# B684X.net
KiCad netlist of a schematic drawn in EAGLE
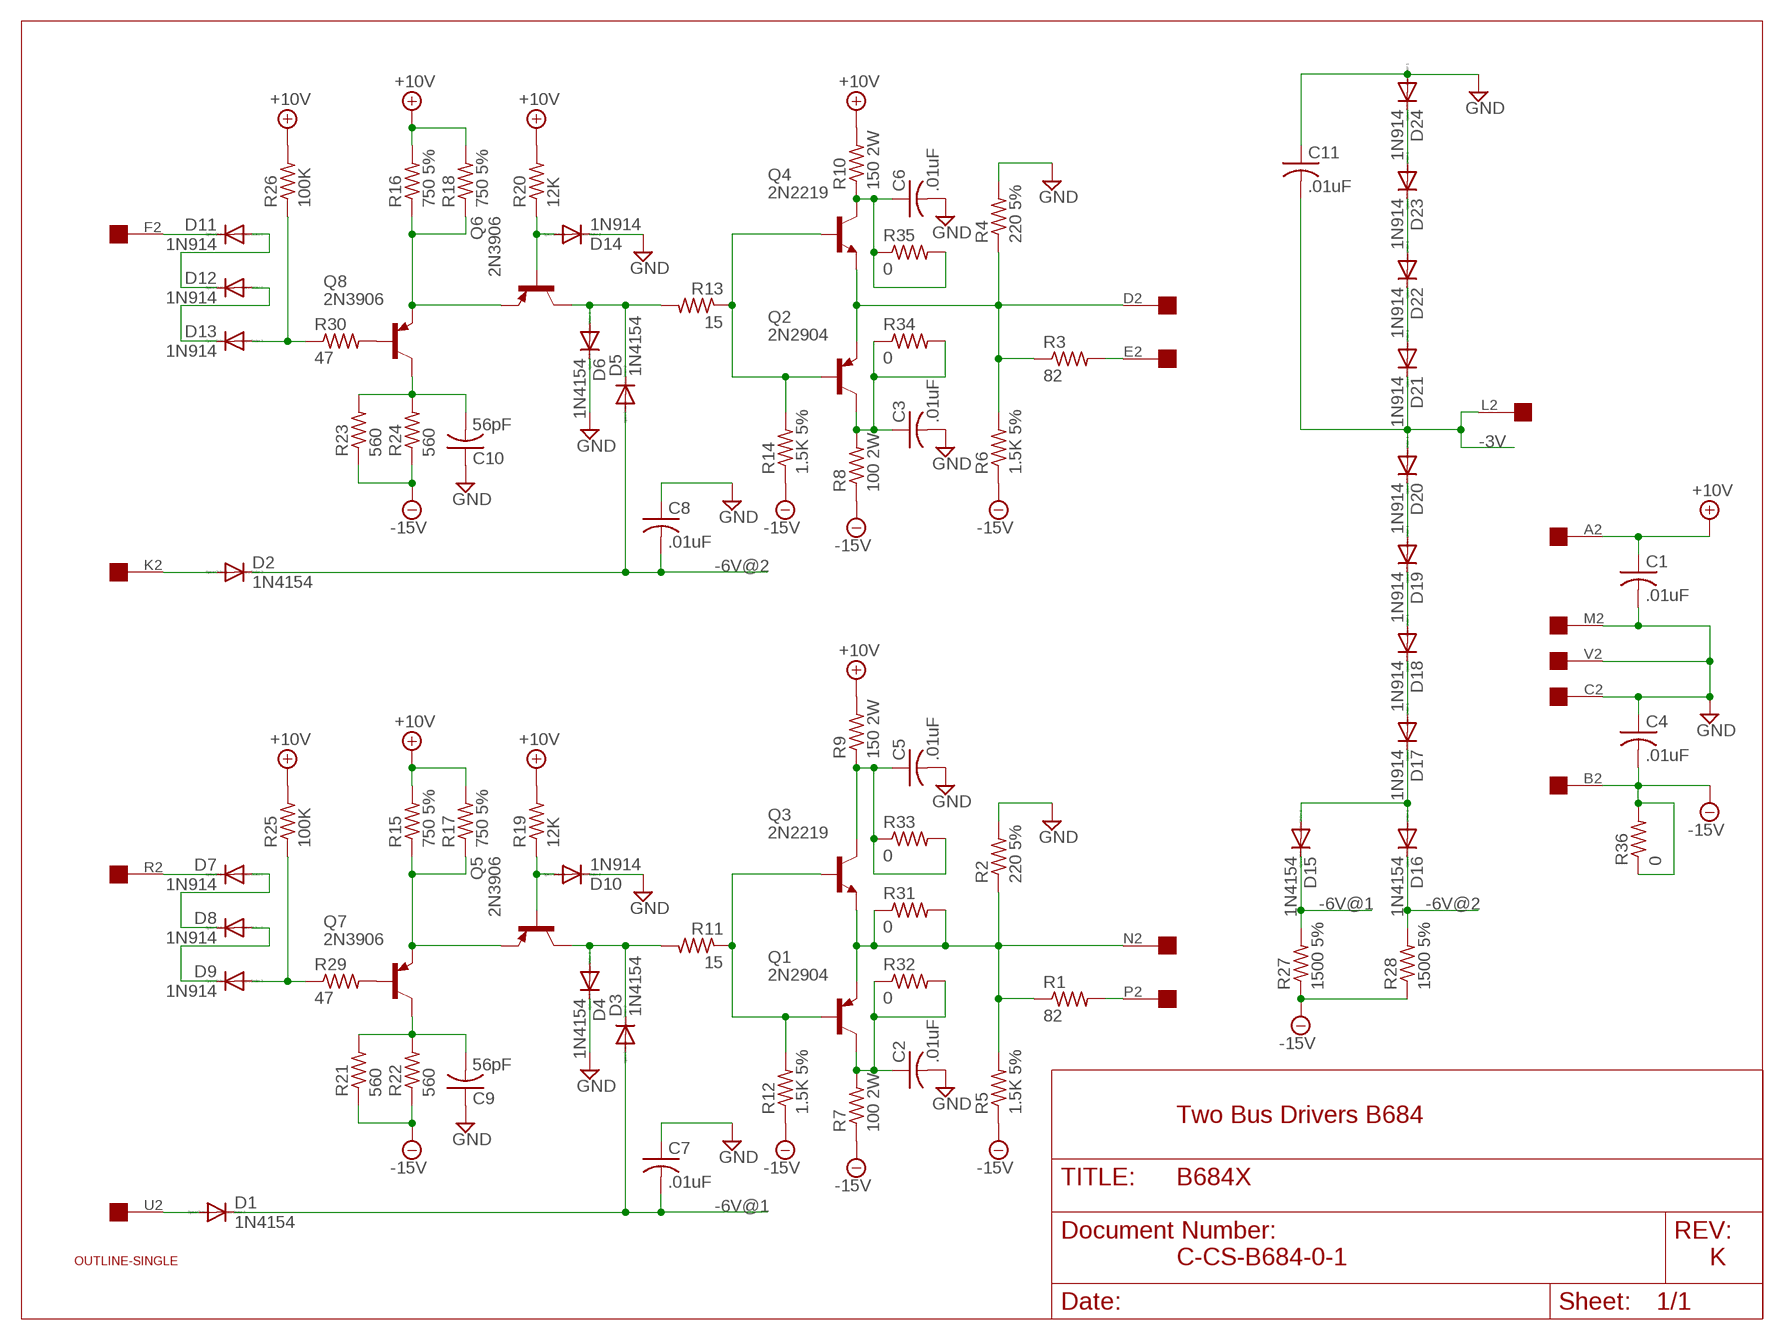
[diagram p0: schematic, sheet 1]

(export (version "E")
  (design (tool "Eeschema 10.0.6"))
  (components
    (comp (ref "C1")
      (value ".01uF")
      (footprint "eagle-import:C063-025X075")
      (libsource (lib "eagle-import") (part "C-US"))
    )
    (comp (ref "C2")
      (value ".01uF")
      (footprint "eagle-import:C063-025X075")
      (libsource (lib "eagle-import") (part "C-US"))
    )
    (comp (ref "C3")
      (value ".01uF")
      (footprint "eagle-import:C063-025X075")
      (libsource (lib "eagle-import") (part "C-US"))
    )
    (comp (ref "C4")
      (value ".01uF")
      (footprint "eagle-import:C063-025X075")
      (libsource (lib "eagle-import") (part "C-US"))
    )
    (comp (ref "C5")
      (value ".01uF")
      (footprint "eagle-import:C063-025X075")
      (libsource (lib "eagle-import") (part "C-US"))
    )
    (comp (ref "C6")
      (value ".01uF")
      (footprint "eagle-import:C063-025X075")
      (libsource (lib "eagle-import") (part "C-US"))
    )
    (comp (ref "C7")
      (value ".01uF")
      (footprint "eagle-import:C063-025X075")
      (libsource (lib "eagle-import") (part "C-US"))
    )
    (comp (ref "C8")
      (value ".01uF")
      (footprint "eagle-import:C063-025X075")
      (libsource (lib "eagle-import") (part "C-US"))
    )
    (comp (ref "C9")
      (value "56pF")
      (footprint "eagle-import:C063-025X075")
      (libsource (lib "eagle-import") (part "C-US"))
    )
    (comp (ref "C10")
      (value "56pF")
      (footprint "eagle-import:C063-025X075")
      (libsource (lib "eagle-import") (part "C-US"))
    )
    (comp (ref "C11")
      (value ".01uF")
      (footprint "eagle-import:C063-025X075")
      (libsource (lib "eagle-import") (part "C-US"))
    )
    (comp (ref "D1")
      (value "1N4154")
      (footprint "eagle-import:DO35-10")
      (libsource (lib "eagle-import") (part "1N4148DO35-10"))
    )
    (comp (ref "D2")
      (value "1N4154")
      (footprint "eagle-import:DO35-10")
      (libsource (lib "eagle-import") (part "1N4148DO35-10"))
    )
    (comp (ref "D3")
      (value "1N4154")
      (footprint "eagle-import:DO35-10")
      (libsource (lib "eagle-import") (part "1N4148DO35-10"))
    )
    (comp (ref "D4")
      (value "1N4154")
      (footprint "eagle-import:DO35-10")
      (libsource (lib "eagle-import") (part "1N4148DO35-10"))
    )
    (comp (ref "D5")
      (value "1N4154")
      (footprint "eagle-import:DO35-10")
      (libsource (lib "eagle-import") (part "1N4148DO35-10"))
    )
    (comp (ref "D6")
      (value "1N4154")
      (footprint "eagle-import:DO35-10")
      (libsource (lib "eagle-import") (part "1N4148DO35-10"))
    )
    (comp (ref "D7")
      (value "1N914")
      (footprint "eagle-import:DO35-10")
      (libsource (lib "eagle-import") (part "1N4148DO35-10"))
    )
    (comp (ref "D8")
      (value "1N914")
      (footprint "eagle-import:DO35-10")
      (libsource (lib "eagle-import") (part "1N4148DO35-10"))
    )
    (comp (ref "D9")
      (value "1N914")
      (footprint "eagle-import:DO35-10")
      (libsource (lib "eagle-import") (part "DIODE-DO35-10"))
    )
    (comp (ref "D10")
      (value "1N914")
      (footprint "eagle-import:DO35-10")
      (libsource (lib "eagle-import") (part "1N4148DO35-10"))
    )
    (comp (ref "D11")
      (value "1N914")
      (footprint "eagle-import:DO35-10")
      (libsource (lib "eagle-import") (part "1N4148DO35-10"))
    )
    (comp (ref "D12")
      (value "1N914")
      (footprint "eagle-import:DO35-10")
      (libsource (lib "eagle-import") (part "1N4148DO35-10"))
    )
    (comp (ref "D13")
      (value "1N914")
      (footprint "eagle-import:DO35-10")
      (libsource (lib "eagle-import") (part "DIODE-DO35-10"))
    )
    (comp (ref "D14")
      (value "1N914")
      (footprint "eagle-import:DO35-10")
      (libsource (lib "eagle-import") (part "1N4148DO35-10"))
    )
    (comp (ref "D15")
      (value "1N4154")
      (footprint "eagle-import:DO35-10")
      (libsource (lib "eagle-import") (part "1N4148DO35-10"))
    )
    (comp (ref "D16")
      (value "1N4154")
      (footprint "eagle-import:DO35-10")
      (libsource (lib "eagle-import") (part "1N4148DO35-10"))
    )
    (comp (ref "D17")
      (value "1N914")
      (footprint "eagle-import:DO35-10")
      (libsource (lib "eagle-import") (part "1N4148DO35-10"))
    )
    (comp (ref "D18")
      (value "1N914")
      (footprint "eagle-import:DO35-10")
      (libsource (lib "eagle-import") (part "1N4148DO35-10"))
    )
    (comp (ref "D19")
      (value "1N914")
      (footprint "eagle-import:DO35-10")
      (libsource (lib "eagle-import") (part "1N4148DO35-10"))
    )
    (comp (ref "D20")
      (value "1N914")
      (footprint "eagle-import:DO35-10")
      (libsource (lib "eagle-import") (part "1N4148DO35-10"))
    )
    (comp (ref "D21")
      (value "1N914")
      (footprint "eagle-import:DO35-10")
      (libsource (lib "eagle-import") (part "1N4148DO35-10"))
    )
    (comp (ref "D22")
      (value "1N914")
      (footprint "eagle-import:DO35-10")
      (libsource (lib "eagle-import") (part "1N4148DO35-10"))
    )
    (comp (ref "D23")
      (value "1N914")
      (footprint "eagle-import:DO35-10")
      (libsource (lib "eagle-import") (part "1N4148DO35-10"))
    )
    (comp (ref "D24")
      (value "1N914")
      (footprint "eagle-import:DO35-10")
      (libsource (lib "eagle-import") (part "1N4148DO35-10"))
    )
    (comp (ref "Q1")
      (value "2N2904")
      (footprint "eagle-import:TO39")
      (libsource (lib "eagle-import") (part "2N3637"))
    )
    (comp (ref "Q2")
      (value "2N2904")
      (footprint "eagle-import:TO39")
      (libsource (lib "eagle-import") (part "2N3637"))
    )
    (comp (ref "Q3")
      (value "2N2219")
      (footprint "eagle-import:TO5")
      (libsource (lib "eagle-import") (part "2N2219"))
    )
    (comp (ref "Q4")
      (value "2N2219")
      (footprint "eagle-import:TO5")
      (libsource (lib "eagle-import") (part "2N2219"))
    )
    (comp (ref "Q5")
      (value "2N3906")
      (footprint "eagle-import:TO39")
      (libsource (lib "eagle-import") (part "2N3637"))
    )
    (comp (ref "Q6")
      (value "2N3906")
      (footprint "eagle-import:TO39")
      (libsource (lib "eagle-import") (part "2N3637"))
    )
    (comp (ref "Q7")
      (value "2N3906")
      (footprint "eagle-import:TO39")
      (libsource (lib "eagle-import") (part "2N3637"))
    )
    (comp (ref "Q8")
      (value "2N3906")
      (footprint "eagle-import:TO39")
      (libsource (lib "eagle-import") (part "2N3637"))
    )
    (comp (ref "R1")
      (value "82")
      (footprint "eagle-import:0207_10")
      (libsource (lib "eagle-import") (part "R-US_0207/10"))
    )
    (comp (ref "R2")
      (value "220 5%")
      (footprint "eagle-import:0207_10")
      (libsource (lib "eagle-import") (part "R-US_0207/10"))
    )
    (comp (ref "R3")
      (value "82")
      (footprint "eagle-import:0207_10")
      (libsource (lib "eagle-import") (part "R-US_0207/10"))
    )
    (comp (ref "R4")
      (value "220 5%")
      (footprint "eagle-import:0207_10")
      (libsource (lib "eagle-import") (part "R-US_0207/10"))
    )
    (comp (ref "R5")
      (value "1.5K 5%")
      (footprint "eagle-import:0207_10")
      (libsource (lib "eagle-import") (part "R-US_0207/10"))
    )
    (comp (ref "R6")
      (value "1.5K 5%")
      (footprint "eagle-import:0207_10")
      (libsource (lib "eagle-import") (part "R-US_0207/10"))
    )
    (comp (ref "R7")
      (value "100 2W")
      (footprint "eagle-import:P0817_22")
      (libsource (lib "eagle-import") (part "R-US_0817/22"))
    )
    (comp (ref "R8")
      (value "100 2W")
      (footprint "eagle-import:P0817_22")
      (libsource (lib "eagle-import") (part "R-US_0817/22"))
    )
    (comp (ref "R9")
      (value "150 2W")
      (footprint "eagle-import:P0817_22")
      (libsource (lib "eagle-import") (part "R-US_0817/22"))
    )
    (comp (ref "R10")
      (value "150 2W")
      (footprint "eagle-import:P0817_22")
      (libsource (lib "eagle-import") (part "R-US_0817/22"))
    )
    (comp (ref "R11")
      (value "15")
      (footprint "eagle-import:0207_10")
      (libsource (lib "eagle-import") (part "R-US_0207/10"))
    )
    (comp (ref "R12")
      (value "1.5K 5%")
      (footprint "eagle-import:0207_10")
      (libsource (lib "eagle-import") (part "R-US_0207/10"))
    )
    (comp (ref "R13")
      (value "15")
      (footprint "eagle-import:0207_10")
      (libsource (lib "eagle-import") (part "R-US_0207/10"))
    )
    (comp (ref "R14")
      (value "1.5K 5%")
      (footprint "eagle-import:0207_10")
      (libsource (lib "eagle-import") (part "R-US_0207/10"))
    )
    (comp (ref "R15")
      (value "750 5%")
      (footprint "eagle-import:0207_10")
      (libsource (lib "eagle-import") (part "R-US_0207/10"))
    )
    (comp (ref "R16")
      (value "750 5%")
      (footprint "eagle-import:0207_10")
      (libsource (lib "eagle-import") (part "R-US_0207/10"))
    )
    (comp (ref "R17")
      (value "750 5%")
      (footprint "eagle-import:0207_10")
      (libsource (lib "eagle-import") (part "R-US_0207/10"))
    )
    (comp (ref "R18")
      (value "750 5%")
      (footprint "eagle-import:0207_10")
      (libsource (lib "eagle-import") (part "R-US_0207/10"))
    )
    (comp (ref "R19")
      (value "12K")
      (footprint "eagle-import:0207_10")
      (libsource (lib "eagle-import") (part "R-US_0207/10"))
    )
    (comp (ref "R20")
      (value "12K")
      (footprint "eagle-import:0207_10")
      (libsource (lib "eagle-import") (part "R-US_0207/10"))
    )
    (comp (ref "R21")
      (value "560")
      (footprint "eagle-import:0207_10")
      (libsource (lib "eagle-import") (part "R-US_0207/10"))
    )
    (comp (ref "R22")
      (value "560")
      (footprint "eagle-import:0207_10")
      (libsource (lib "eagle-import") (part "R-US_0207/10"))
    )
    (comp (ref "R23")
      (value "560")
      (footprint "eagle-import:0207_10")
      (libsource (lib "eagle-import") (part "R-US_0207/10"))
    )
    (comp (ref "R24")
      (value "560")
      (footprint "eagle-import:0207_10")
      (libsource (lib "eagle-import") (part "R-US_0207/10"))
    )
    (comp (ref "R25")
      (value "100K")
      (footprint "eagle-import:0207_10")
      (libsource (lib "eagle-import") (part "R-US_0207/10"))
    )
    (comp (ref "R26")
      (value "100K")
      (footprint "eagle-import:0207_10")
      (libsource (lib "eagle-import") (part "R-US_0207/10"))
    )
    (comp (ref "R27")
      (value "1500 5%")
      (footprint "eagle-import:0207_10")
      (libsource (lib "eagle-import") (part "R-US_0207/10"))
    )
    (comp (ref "R28")
      (value "1500 5%")
      (footprint "eagle-import:0207_10")
      (libsource (lib "eagle-import") (part "R-US_0207/10"))
    )
    (comp (ref "R29")
      (value "47")
      (footprint "eagle-import:0207_10")
      (libsource (lib "eagle-import") (part "R-US_0207/10"))
    )
    (comp (ref "R30")
      (value "47")
      (footprint "eagle-import:0207_10")
      (libsource (lib "eagle-import") (part "R-US_0207/10"))
    )
    (comp (ref "R31")
      (value "0")
      (footprint "eagle-import:0207_10")
      (libsource (lib "eagle-import") (part "R-US_0207/10"))
    )
    (comp (ref "R32")
      (value "0")
      (footprint "eagle-import:0207_10")
      (libsource (lib "eagle-import") (part "R-US_0207/10"))
    )
    (comp (ref "R33")
      (value "0")
      (footprint "eagle-import:0207_10")
      (libsource (lib "eagle-import") (part "R-US_0207/10"))
    )
    (comp (ref "R34")
      (value "0")
      (footprint "eagle-import:0207_10")
      (libsource (lib "eagle-import") (part "R-US_0207/10"))
    )
    (comp (ref "R35")
      (value "0")
      (footprint "eagle-import:0207_10")
      (libsource (lib "eagle-import") (part "R-US_0207/10"))
    )
    (comp (ref "R36")
      (value "0")
      (footprint "eagle-import:0207_10")
      (libsource (lib "eagle-import") (part "R-US_0207/10"))
    )
    (comp (ref "U$1")
      (value "OUTLINE-SINGLE")
      (footprint "eagle-import:SINGLE")
      (libsource (lib "eagle-import") (part "OUTLINE-SINGLE"))
    )
    (comp (ref "U$2")
      (value "EDGE-1")
      (footprint "eagle-import:EDGE-CON1")
      (libsource (lib "eagle-import") (part "EDGE-1"))
    )
  )
  (nets
    (net (code "1") (name "+10V") (class "Default")
      (node (ref "C1") (pin "1") (pinfunction "1_1") (pintype "passive"))
      (node (ref "R10") (pin "2") (pinfunction "2_2") (pintype "passive"))
      (node (ref "R15") (pin "2") (pinfunction "2_2") (pintype "passive"))
      (node (ref "R16") (pin "2") (pinfunction "2_2") (pintype "passive"))
      (node (ref "R17") (pin "2") (pinfunction "2_2") (pintype "passive"))
      (node (ref "R18") (pin "2") (pinfunction "2_2") (pintype "passive"))
      (node (ref "R19") (pin "2") (pinfunction "2_2") (pintype "passive"))
      (node (ref "R20") (pin "2") (pinfunction "2_2") (pintype "passive"))
      (node (ref "R25") (pin "2") (pinfunction "2_2") (pintype "passive"))
      (node (ref "R26") (pin "2") (pinfunction "2_2") (pintype "passive"))
      (node (ref "R9") (pin "2") (pinfunction "2_2") (pintype "passive"))
      (node (ref "U$2") (pin "A2") (pinfunction "1_A2") (pintype "bidirectional"))
    )
    (net (code "2") (name "-15V") (class "Default")
      (node (ref "C4") (pin "2") (pinfunction "2_2") (pintype "passive"))
      (node (ref "R12") (pin "1") (pinfunction "1_1") (pintype "passive"))
      (node (ref "R14") (pin "1") (pinfunction "1_1") (pintype "passive"))
      (node (ref "R21") (pin "1") (pinfunction "1_1") (pintype "passive"))
      (node (ref "R22") (pin "1") (pinfunction "1_1") (pintype "passive"))
      (node (ref "R23") (pin "1") (pinfunction "1_1") (pintype "passive"))
      (node (ref "R24") (pin "1") (pinfunction "1_1") (pintype "passive"))
      (node (ref "R27") (pin "1") (pinfunction "1_1") (pintype "passive"))
      (node (ref "R28") (pin "1") (pinfunction "1_1") (pintype "passive"))
      (node (ref "R36") (pin "1") (pinfunction "1_1") (pintype "passive"))
      (node (ref "R36") (pin "2") (pinfunction "2_2") (pintype "passive"))
      (node (ref "R5") (pin "1") (pinfunction "1_1") (pintype "passive"))
      (node (ref "R6") (pin "1") (pinfunction "1_1") (pintype "passive"))
      (node (ref "R7") (pin "1") (pinfunction "1_1") (pintype "passive"))
      (node (ref "R8") (pin "1") (pinfunction "1_1") (pintype "passive"))
      (node (ref "U$2") (pin "B2") (pinfunction "1_B2") (pintype "bidirectional"))
    )
    (net (code "3") (name "/-3V") (class "Default")
      (node (ref "C11") (pin "2") (pinfunction "2_2") (pintype "passive"))
      (node (ref "D20") (pin "A") (pinfunction "A_A") (pintype "passive"))
      (node (ref "D21") (pin "C") (pinfunction "C_C") (pintype "passive"))
      (node (ref "U$2") (pin "L2") (pinfunction "1_L2") (pintype "bidirectional"))
    )
    (net (code "4") (name "/-6V@1") (class "Default")
      (node (ref "C7") (pin "2") (pinfunction "2_2") (pintype "passive"))
      (node (ref "D1") (pin "C") (pinfunction "C_C") (pintype "passive"))
      (node (ref "D15") (pin "C") (pinfunction "C_C") (pintype "passive"))
      (node (ref "D3") (pin "A") (pinfunction "A_A") (pintype "passive"))
      (node (ref "R27") (pin "2") (pinfunction "2_2") (pintype "passive"))
    )
    (net (code "5") (name "/-6V@2") (class "Default")
      (node (ref "C8") (pin "2") (pinfunction "2_2") (pintype "passive"))
      (node (ref "D16") (pin "C") (pinfunction "C_C") (pintype "passive"))
      (node (ref "D2") (pin "C") (pinfunction "C_C") (pintype "passive"))
      (node (ref "D5") (pin "A") (pinfunction "A_A") (pintype "passive"))
      (node (ref "R28") (pin "2") (pinfunction "2_2") (pintype "passive"))
    )
    (net (code "6") (name "GND") (class "Default")
      (node (ref "C1") (pin "2") (pinfunction "2_2") (pintype "passive"))
      (node (ref "C10") (pin "1") (pinfunction "1_1") (pintype "passive"))
      (node (ref "C11") (pin "1") (pinfunction "1_1") (pintype "passive"))
      (node (ref "C2") (pin "2") (pinfunction "2_2") (pintype "passive"))
      (node (ref "C3") (pin "2") (pinfunction "2_2") (pintype "passive"))
      (node (ref "C4") (pin "1") (pinfunction "1_1") (pintype "passive"))
      (node (ref "C5") (pin "2") (pinfunction "2_2") (pintype "passive"))
      (node (ref "C6") (pin "2") (pinfunction "2_2") (pintype "passive"))
      (node (ref "C7") (pin "1") (pinfunction "1_1") (pintype "passive"))
      (node (ref "C8") (pin "1") (pinfunction "1_1") (pintype "passive"))
      (node (ref "C9") (pin "1") (pinfunction "1_1") (pintype "passive"))
      (node (ref "D10") (pin "C") (pinfunction "C_C") (pintype "passive"))
      (node (ref "D14") (pin "C") (pinfunction "C_C") (pintype "passive"))
      (node (ref "D24") (pin "A") (pinfunction "A_A") (pintype "passive"))
      (node (ref "D4") (pin "C") (pinfunction "C_C") (pintype "passive"))
      (node (ref "D6") (pin "C") (pinfunction "C_C") (pintype "passive"))
      (node (ref "R2") (pin "2") (pinfunction "2_2") (pintype "passive"))
      (node (ref "R4") (pin "2") (pinfunction "2_2") (pintype "passive"))
      (node (ref "U$2") (pin "C2") (pinfunction "1_C2") (pintype "bidirectional"))
      (node (ref "U$2") (pin "M2") (pinfunction "1_M2") (pintype "bidirectional"))
      (node (ref "U$2") (pin "V2") (pinfunction "1_V2") (pintype "bidirectional"))
    )
    (net (code "7") (name "Net-(D7-PadA)") (class "Default")
      (node (ref "D7") (pin "A") (pinfunction "A_A") (pintype "passive"))
      (node (ref "D8") (pin "C") (pinfunction "C_C") (pintype "passive"))
    )
    (net (code "8") (name "Net-(D8-PadA)") (class "Default")
      (node (ref "D8") (pin "A") (pinfunction "A_A") (pintype "passive"))
      (node (ref "D9") (pin "C") (pinfunction "C_C") (pintype "passive"))
    )
    (net (code "9") (name "Net-(D9-PadA)") (class "Default")
      (node (ref "D9") (pin "A") (pinfunction "A_A") (pintype "passive"))
      (node (ref "R25") (pin "1") (pinfunction "1_1") (pintype "passive"))
      (node (ref "R29") (pin "1") (pinfunction "1_1") (pintype "passive"))
    )
    (net (code "10") (name "Net-(D11-PadA)") (class "Default")
      (node (ref "D11") (pin "A") (pinfunction "A_A") (pintype "passive"))
      (node (ref "D12") (pin "C") (pinfunction "C_C") (pintype "passive"))
    )
    (net (code "11") (name "Net-(D12-PadA)") (class "Default")
      (node (ref "D12") (pin "A") (pinfunction "A_A") (pintype "passive"))
      (node (ref "D13") (pin "C") (pinfunction "C_C") (pintype "passive"))
    )
    (net (code "12") (name "Net-(D13-PadA)") (class "Default")
      (node (ref "D13") (pin "A") (pinfunction "A_A") (pintype "passive"))
      (node (ref "R26") (pin "1") (pinfunction "1_1") (pintype "passive"))
      (node (ref "R30") (pin "1") (pinfunction "1_1") (pintype "passive"))
    )
    (net (code "13") (name "Net-(D15-PadA)") (class "Default")
      (node (ref "D15") (pin "A") (pinfunction "A_A") (pintype "passive"))
      (node (ref "D16") (pin "A") (pinfunction "A_A") (pintype "passive"))
      (node (ref "D17") (pin "C") (pinfunction "C_C") (pintype "passive"))
    )
    (net (code "14") (name "Net-(D17-PadA)") (class "Default")
      (node (ref "D17") (pin "A") (pinfunction "A_A") (pintype "passive"))
      (node (ref "D18") (pin "C") (pinfunction "C_C") (pintype "passive"))
    )
    (net (code "15") (name "Net-(D18-PadA)") (class "Default")
      (node (ref "D18") (pin "A") (pinfunction "A_A") (pintype "passive"))
      (node (ref "D19") (pin "C") (pinfunction "C_C") (pintype "passive"))
    )
    (net (code "16") (name "Net-(D19-PadA)") (class "Default")
      (node (ref "D19") (pin "A") (pinfunction "A_A") (pintype "passive"))
      (node (ref "D20") (pin "C") (pinfunction "C_C") (pintype "passive"))
    )
    (net (code "17") (name "Net-(D21-PadA)") (class "Default")
      (node (ref "D21") (pin "A") (pinfunction "A_A") (pintype "passive"))
      (node (ref "D22") (pin "C") (pinfunction "C_C") (pintype "passive"))
    )
    (net (code "18") (name "Net-(D22-PadA)") (class "Default")
      (node (ref "D22") (pin "A") (pinfunction "A_A") (pintype "passive"))
      (node (ref "D23") (pin "C") (pinfunction "C_C") (pintype "passive"))
    )
    (net (code "19") (name "Net-(D23-PadA)") (class "Default")
      (node (ref "D23") (pin "A") (pinfunction "A_A") (pintype "passive"))
      (node (ref "D24") (pin "C") (pinfunction "C_C") (pintype "passive"))
    )
    (net (code "20") (name "Net-(Q1-B)") (class "Default")
      (node (ref "Q1") (pin "2") (pinfunction "B_2") (pintype "passive"))
      (node (ref "Q3") (pin "2") (pinfunction "B_2") (pintype "passive"))
      (node (ref "R11") (pin "1") (pinfunction "1_1") (pintype "passive"))
      (node (ref "R12") (pin "2") (pinfunction "2_2") (pintype "passive"))
    )
    (net (code "21") (name "Net-(Q1-C)") (class "Default")
      (node (ref "C2") (pin "1") (pinfunction "1_1") (pintype "passive"))
      (node (ref "Q1") (pin "3") (pinfunction "C_3") (pintype "passive"))
      (node (ref "R32") (pin "1") (pinfunction "1_1") (pintype "passive"))
      (node (ref "R32") (pin "2") (pinfunction "2_2") (pintype "passive"))
      (node (ref "R7") (pin "2") (pinfunction "2_2") (pintype "passive"))
    )
    (net (code "22") (name "Net-(Q1-E)") (class "Default")
      (node (ref "Q1") (pin "1") (pinfunction "E_1") (pintype "passive"))
      (node (ref "Q3") (pin "1") (pinfunction "E_1") (pintype "passive"))
      (node (ref "R1") (pin "1") (pinfunction "1_1") (pintype "passive"))
      (node (ref "R2") (pin "1") (pinfunction "1_1") (pintype "passive"))
      (node (ref "R31") (pin "1") (pinfunction "1_1") (pintype "passive"))
      (node (ref "R31") (pin "2") (pinfunction "2_2") (pintype "passive"))
      (node (ref "R5") (pin "2") (pinfunction "2_2") (pintype "passive"))
      (node (ref "U$2") (pin "N2") (pinfunction "1_N2") (pintype "bidirectional"))
    )
    (net (code "23") (name "Net-(Q2-B)") (class "Default")
      (node (ref "Q2") (pin "2") (pinfunction "B_2") (pintype "passive"))
      (node (ref "Q4") (pin "2") (pinfunction "B_2") (pintype "passive"))
      (node (ref "R13") (pin "1") (pinfunction "1_1") (pintype "passive"))
      (node (ref "R14") (pin "2") (pinfunction "2_2") (pintype "passive"))
    )
    (net (code "24") (name "Net-(Q2-C)") (class "Default")
      (node (ref "C3") (pin "1") (pinfunction "1_1") (pintype "passive"))
      (node (ref "Q2") (pin "3") (pinfunction "C_3") (pintype "passive"))
      (node (ref "R34") (pin "1") (pinfunction "1_1") (pintype "passive"))
      (node (ref "R34") (pin "2") (pinfunction "2_2") (pintype "passive"))
      (node (ref "R8") (pin "2") (pinfunction "2_2") (pintype "passive"))
    )
    (net (code "25") (name "Net-(Q2-E)") (class "Default")
      (node (ref "Q2") (pin "1") (pinfunction "E_1") (pintype "passive"))
      (node (ref "Q4") (pin "1") (pinfunction "E_1") (pintype "passive"))
      (node (ref "R3") (pin "1") (pinfunction "1_1") (pintype "passive"))
      (node (ref "R4") (pin "1") (pinfunction "1_1") (pintype "passive"))
      (node (ref "R6") (pin "2") (pinfunction "2_2") (pintype "passive"))
      (node (ref "U$2") (pin "D2") (pinfunction "1_D2") (pintype "bidirectional"))
    )
    (net (code "26") (name "Net-(Q3-C)") (class "Default")
      (node (ref "C5") (pin "1") (pinfunction "1_1") (pintype "passive"))
      (node (ref "Q3") (pin "3") (pinfunction "C_3") (pintype "passive"))
      (node (ref "R33") (pin "1") (pinfunction "1_1") (pintype "passive"))
      (node (ref "R33") (pin "2") (pinfunction "2_2") (pintype "passive"))
      (node (ref "R9") (pin "1") (pinfunction "1_1") (pintype "passive"))
    )
    (net (code "27") (name "Net-(Q4-C)") (class "Default")
      (node (ref "C6") (pin "1") (pinfunction "1_1") (pintype "passive"))
      (node (ref "Q4") (pin "3") (pinfunction "C_3") (pintype "passive"))
      (node (ref "R10") (pin "1") (pinfunction "1_1") (pintype "passive"))
      (node (ref "R35") (pin "1") (pinfunction "1_1") (pintype "passive"))
      (node (ref "R35") (pin "2") (pinfunction "2_2") (pintype "passive"))
    )
    (net (code "28") (name "Net-(Q5-B)") (class "Default")
      (node (ref "D10") (pin "A") (pinfunction "A_A") (pintype "passive"))
      (node (ref "Q5") (pin "2") (pinfunction "B_2") (pintype "passive"))
      (node (ref "R19") (pin "1") (pinfunction "1_1") (pintype "passive"))
    )
    (net (code "29") (name "Net-(Q5-C)") (class "Default")
      (node (ref "D3") (pin "C") (pinfunction "C_C") (pintype "passive"))
      (node (ref "D4") (pin "A") (pinfunction "A_A") (pintype "passive"))
      (node (ref "Q5") (pin "3") (pinfunction "C_3") (pintype "passive"))
      (node (ref "R11") (pin "2") (pinfunction "2_2") (pintype "passive"))
    )
    (net (code "30") (name "Net-(Q5-E)") (class "Default")
      (node (ref "Q5") (pin "1") (pinfunction "E_1") (pintype "passive"))
      (node (ref "Q7") (pin "1") (pinfunction "E_1") (pintype "passive"))
      (node (ref "R15") (pin "1") (pinfunction "1_1") (pintype "passive"))
      (node (ref "R17") (pin "1") (pinfunction "1_1") (pintype "passive"))
    )
    (net (code "31") (name "Net-(Q6-B)") (class "Default")
      (node (ref "D14") (pin "A") (pinfunction "A_A") (pintype "passive"))
      (node (ref "Q6") (pin "2") (pinfunction "B_2") (pintype "passive"))
      (node (ref "R20") (pin "1") (pinfunction "1_1") (pintype "passive"))
    )
    (net (code "32") (name "Net-(Q6-C)") (class "Default")
      (node (ref "D5") (pin "C") (pinfunction "C_C") (pintype "passive"))
      (node (ref "D6") (pin "A") (pinfunction "A_A") (pintype "passive"))
      (node (ref "Q6") (pin "3") (pinfunction "C_3") (pintype "passive"))
      (node (ref "R13") (pin "2") (pinfunction "2_2") (pintype "passive"))
    )
    (net (code "33") (name "Net-(Q6-E)") (class "Default")
      (node (ref "Q6") (pin "1") (pinfunction "E_1") (pintype "passive"))
      (node (ref "Q8") (pin "1") (pinfunction "E_1") (pintype "passive"))
      (node (ref "R16") (pin "1") (pinfunction "1_1") (pintype "passive"))
      (node (ref "R18") (pin "1") (pinfunction "1_1") (pintype "passive"))
    )
    (net (code "34") (name "Net-(Q7-B)") (class "Default")
      (node (ref "Q7") (pin "2") (pinfunction "B_2") (pintype "passive"))
      (node (ref "R29") (pin "2") (pinfunction "2_2") (pintype "passive"))
    )
    (net (code "35") (name "Net-(Q7-C)") (class "Default")
      (node (ref "C9") (pin "2") (pinfunction "2_2") (pintype "passive"))
      (node (ref "Q7") (pin "3") (pinfunction "C_3") (pintype "passive"))
      (node (ref "R21") (pin "2") (pinfunction "2_2") (pintype "passive"))
      (node (ref "R22") (pin "2") (pinfunction "2_2") (pintype "passive"))
    )
    (net (code "36") (name "Net-(Q8-B)") (class "Default")
      (node (ref "Q8") (pin "2") (pinfunction "B_2") (pintype "passive"))
      (node (ref "R30") (pin "2") (pinfunction "2_2") (pintype "passive"))
    )
    (net (code "37") (name "Net-(Q8-C)") (class "Default")
      (node (ref "C10") (pin "2") (pinfunction "2_2") (pintype "passive"))
      (node (ref "Q8") (pin "3") (pinfunction "C_3") (pintype "passive"))
      (node (ref "R23") (pin "2") (pinfunction "2_2") (pintype "passive"))
      (node (ref "R24") (pin "2") (pinfunction "2_2") (pintype "passive"))
    )
    (net (code "38") (name "Net-(U$2E-1)") (class "Default")
      (node (ref "R3") (pin "2") (pinfunction "2_2") (pintype "passive"))
      (node (ref "U$2") (pin "E2") (pinfunction "1_E2") (pintype "bidirectional"))
    )
    (net (code "39") (name "Net-(U$2F-1)") (class "Default")
      (node (ref "D11") (pin "C") (pinfunction "C_C") (pintype "passive"))
      (node (ref "U$2") (pin "F2") (pinfunction "1_F2") (pintype "bidirectional"))
    )
    (net (code "40") (name "Net-(U$2I-1)") (class "Default")
      (node (ref "D2") (pin "A") (pinfunction "A_A") (pintype "passive"))
      (node (ref "U$2") (pin "K2") (pinfunction "1_K2") (pintype "bidirectional"))
    )
    (net (code "41") (name "Net-(U$2M-1)") (class "Default")
      (node (ref "R1") (pin "2") (pinfunction "2_2") (pintype "passive"))
      (node (ref "U$2") (pin "P2") (pinfunction "1_P2") (pintype "bidirectional"))
    )
    (net (code "42") (name "Net-(U$2N-1)") (class "Default")
      (node (ref "D7") (pin "C") (pinfunction "C_C") (pintype "passive"))
      (node (ref "U$2") (pin "R2") (pinfunction "1_R2") (pintype "bidirectional"))
    )
    (net (code "43") (name "Net-(U$2Q-1)") (class "Default")
      (node (ref "D1") (pin "A") (pinfunction "A_A") (pintype "passive"))
      (node (ref "U$2") (pin "U2") (pinfunction "1_U2") (pintype "bidirectional"))
    )
  )
)
